# LPC55S69_MINI.net
KiCad netlist of a schematic drawn in Altium Designer
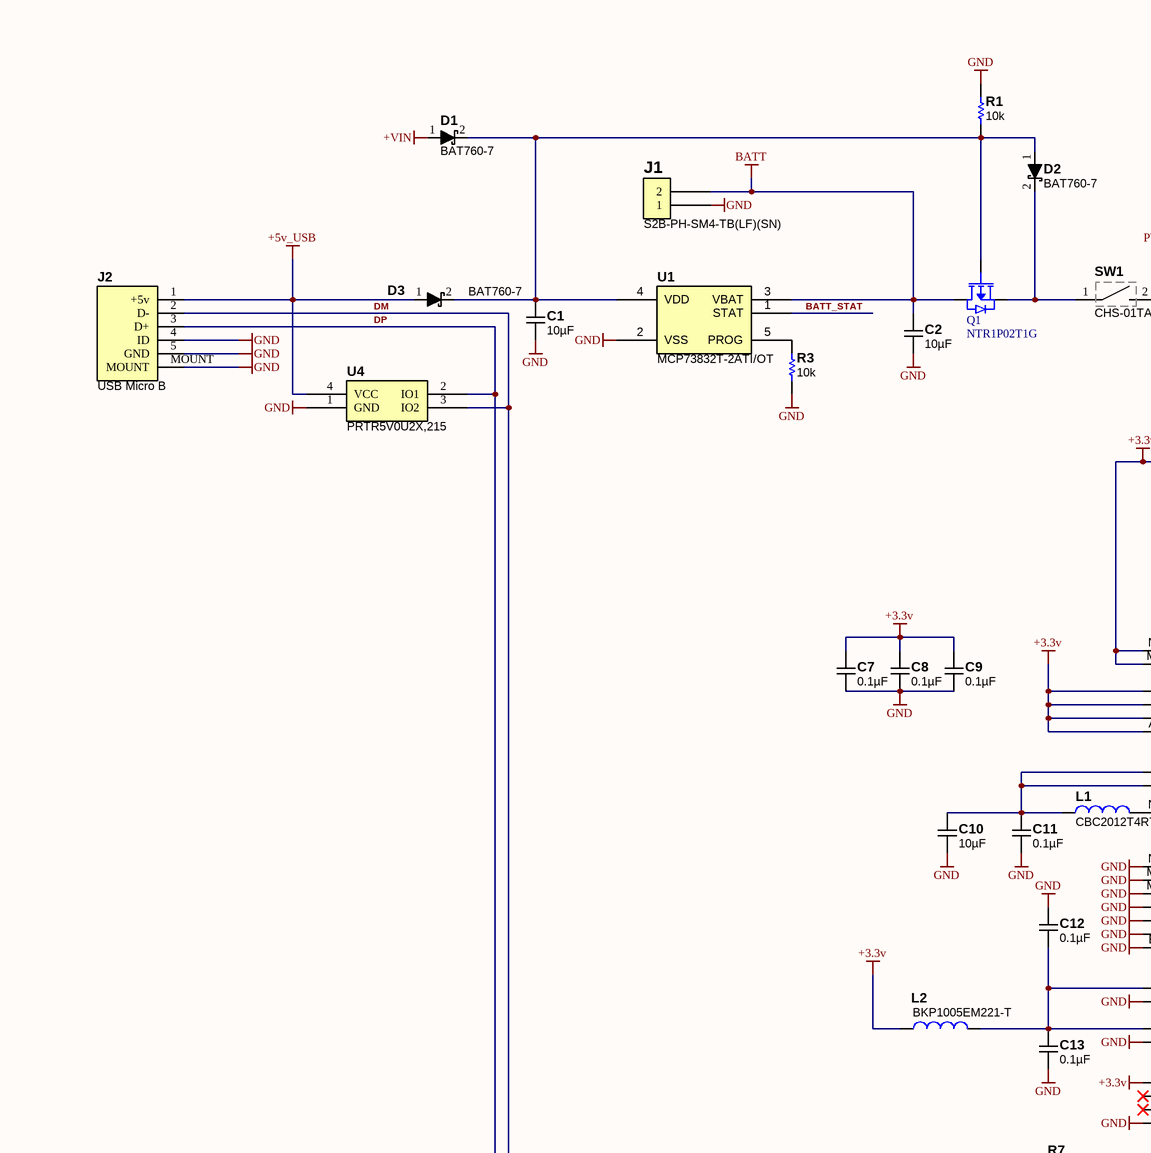
[diagram p0: LPC55S69_MINI.SchDoc, top left]
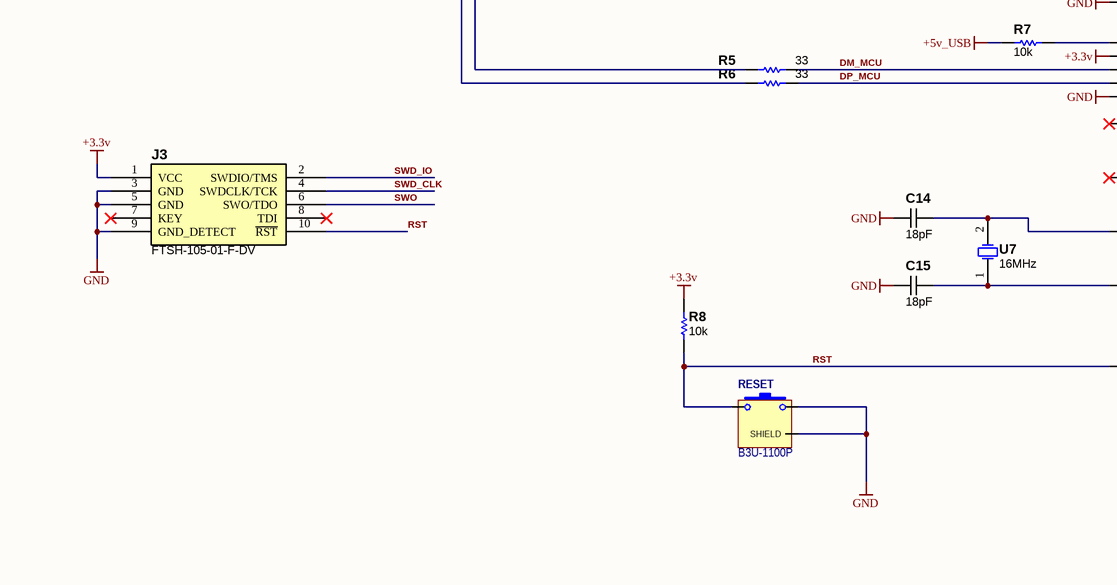
[diagram p1: LPC55S69_MINI.SchDoc, bottom left]
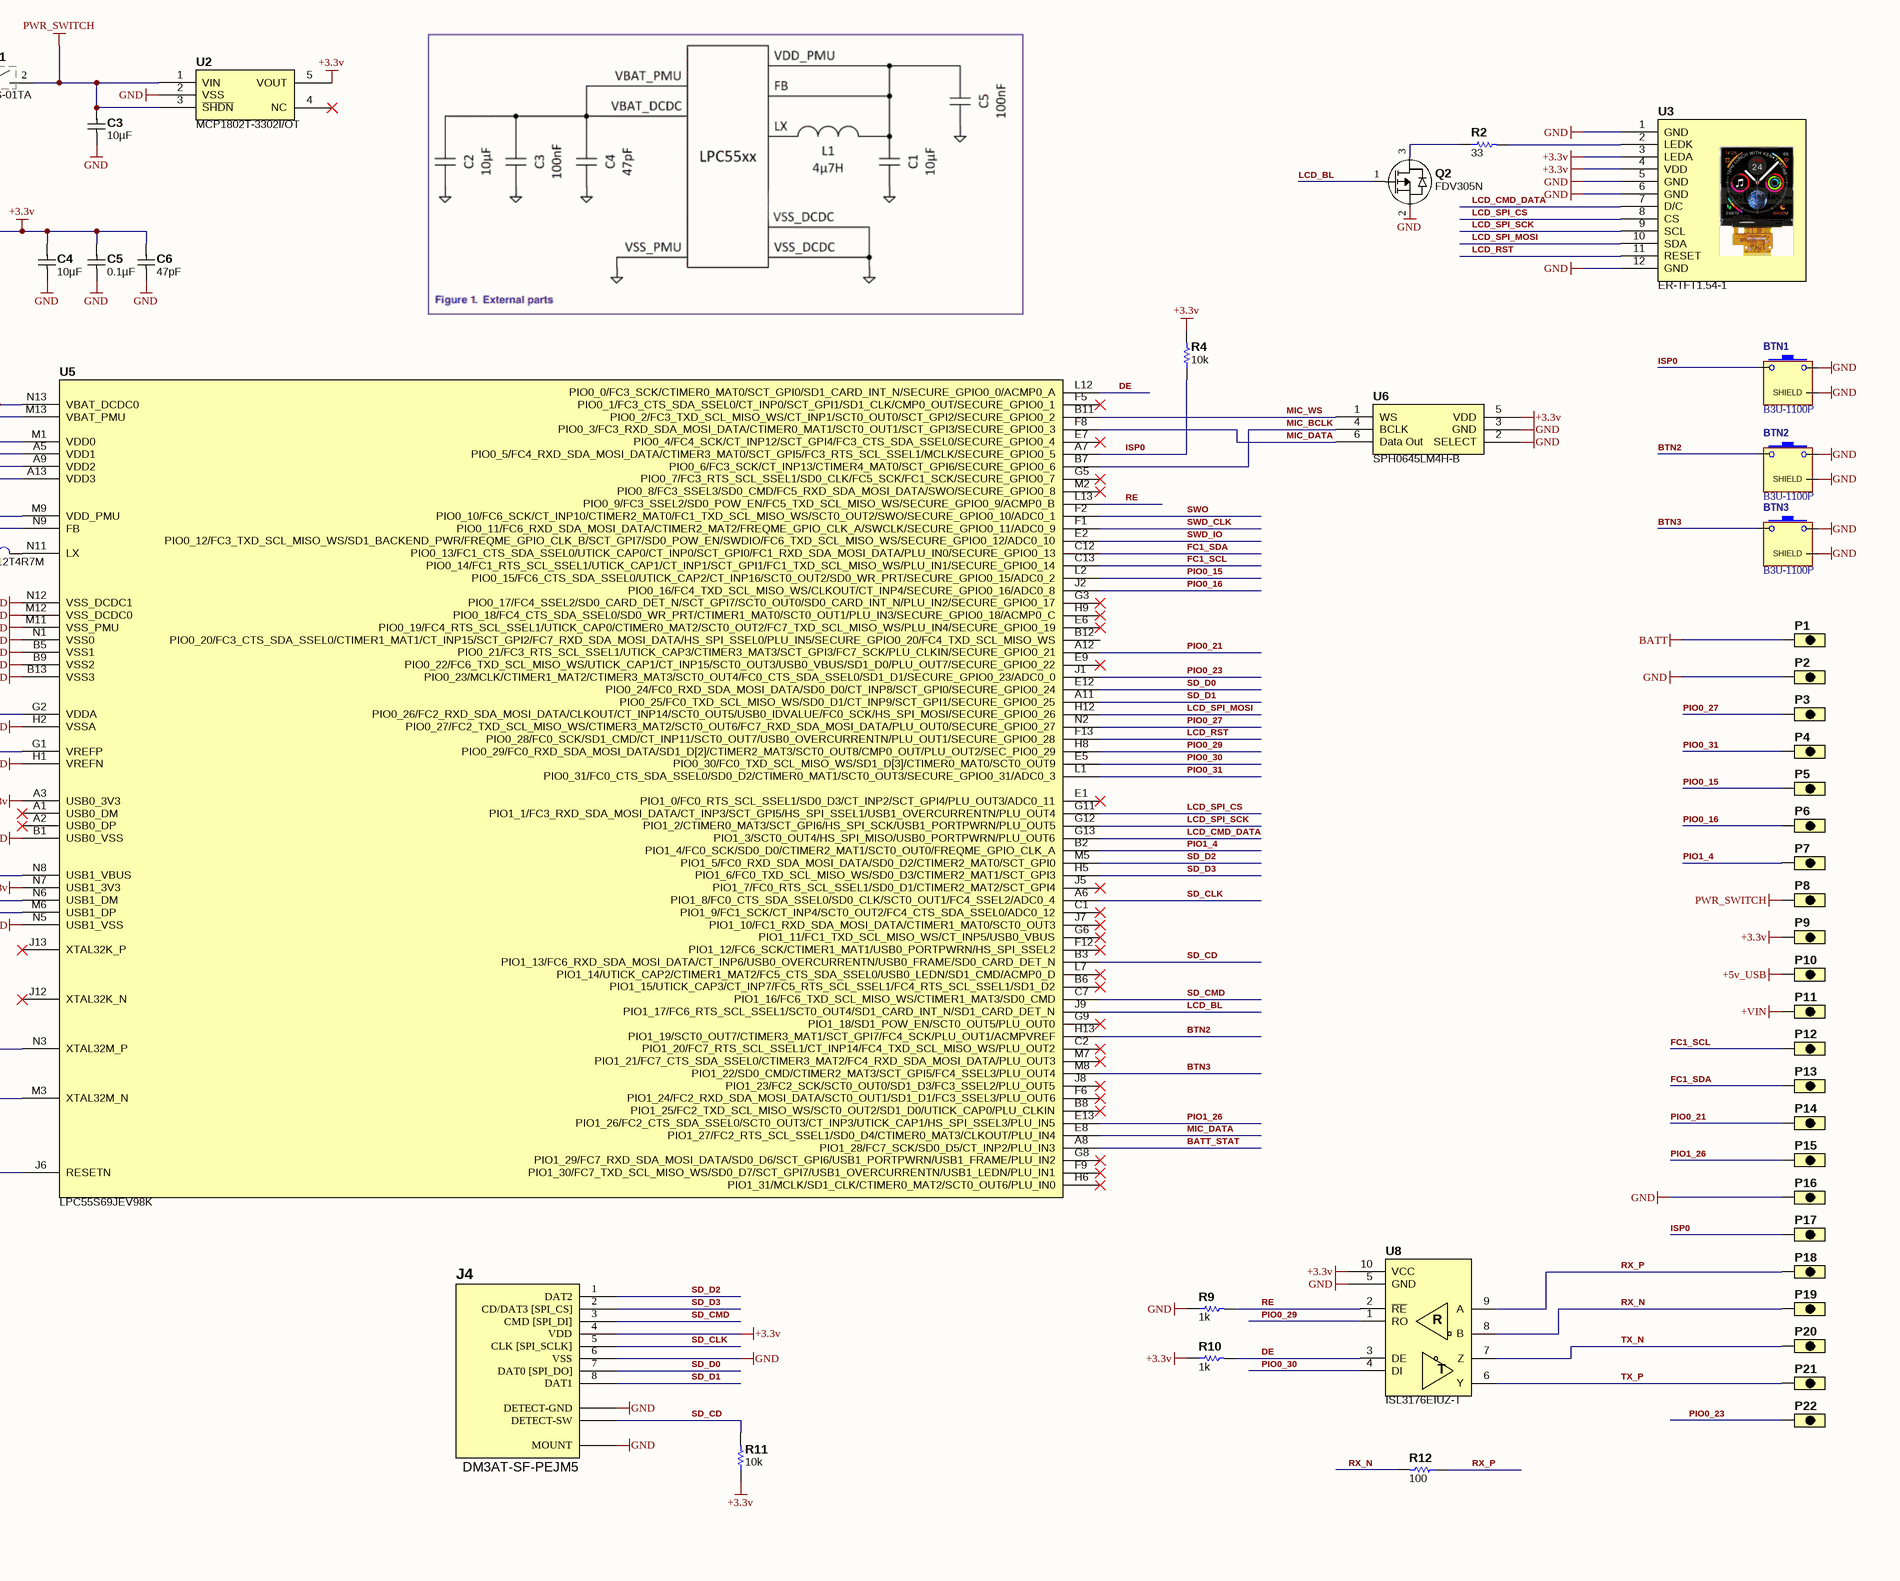
[diagram p2: LPC55S69_MINI.SchDoc, bottom right]

(export (version "E")
  (design (tool "Eeschema 10.0.6"))
  (components
    (comp (ref "BTN1")
      (value "B3U-1100P")
      (footprint "OMRON_B3U-1100P")
      (description "SWITCH TACTILE SPST-NO 0.05A 12V")
      (fields (field (name "MANUFACTURER") "Omron Electronics Inc-EMC Div"))
      (libsource (lib "Switches-N") (part "B3U-1100P"))
    )
    (comp (ref "BTN2")
      (value "B3U-1100P")
      (footprint "OMRON_B3U-1100P")
      (description "SWITCH TACTILE SPST-NO 0.05A 12V")
      (fields (field (name "MANUFACTURER") "Omron Electronics Inc-EMC Div"))
      (libsource (lib "Switches-N") (part "B3U-1100P"))
    )
    (comp (ref "BTN3")
      (value "B3U-1100P")
      (footprint "OMRON_B3U-1100P")
      (description "SWITCH TACTILE SPST-NO 0.05A 12V")
      (fields (field (name "MANUFACTURER") "Omron Electronics Inc-EMC Div"))
      (libsource (lib "Switches-N") (part "B3U-1100P"))
    )
    (comp (ref "C1")
      (value "10µF")
      (footprint "C0805_1.45MM_MD")
      (description "CAP CER 10UF 6.3V X7R 0805")
      (fields
        (field (name "MANUFACTURER PART NUMBER") "CGA4J1X7R0J106K125AC")
        (field (name "MANUFACTURER") "TDK Corporation")
      )
      (libsource (lib "Capacitors - TDK- AEC-Q200") (part "C_2P_NP"))
    )
    (comp (ref "C2")
      (value "10µF")
      (footprint "C0805_1.45MM_MD")
      (description "CAP CER 10UF 6.3V X7R 0805")
      (fields
        (field (name "MANUFACTURER PART NUMBER") "CGA4J1X7R0J106K125AC")
        (field (name "MANUFACTURER") "TDK Corporation")
      )
      (libsource (lib "Capacitors - TDK- AEC-Q200") (part "C_2P_NP"))
    )
    (comp (ref "C3")
      (value "10µF")
      (footprint "C0805_1.45MM_MD")
      (description "CAP CER 10UF 6.3V X7R 0805")
      (fields
        (field (name "MANUFACTURER PART NUMBER") "CGA4J1X7R0J106K125AC")
        (field (name "MANUFACTURER") "TDK Corporation")
      )
      (libsource (lib "Capacitors - TDK- AEC-Q200") (part "C_2P_NP"))
    )
    (comp (ref "C4")
      (value "10µF")
      (footprint "C0805_1.45MM_MD")
      (description "CAP CER 10UF 6.3V X7R 0805")
      (fields
        (field (name "MANUFACTURER PART NUMBER") "CGA4J1X7R0J106K125AC")
        (field (name "MANUFACTURER") "TDK Corporation")
      )
      (libsource (lib "Capacitors - TDK- AEC-Q200") (part "C_2P_NP"))
    )
    (comp (ref "C5")
      (value "0.1µF")
      (footprint "C0402_0.55MM_MD")
      (description "CAP CER 0.1UF 16V X7R 0402")
      (fields
        (field (name "MANUFACTURER PART NUMBER") "CGA2B1X7R1C104K050BC")
        (field (name "MANUFACTURER") "TDK Corporation")
      )
      (libsource (lib "Capacitors - TDK- AEC-Q200") (part "C_2P_NP"))
    )
    (comp (ref "C6")
      (value "47pF")
      (footprint "C0402_0.55MM_MD")
      (description "CAP CER 47PF 50V C0G 0402")
      (fields
        (field (name "MANUFACTURER PART NUMBER") "CGA2B2C0G1H470J050BA")
        (field (name "MANUFACTURER") "TDK Corporation")
      )
      (libsource (lib "Capacitors - TDK- AEC-Q200") (part "C_2P_NP"))
    )
    (comp (ref "C7")
      (value "0.1µF")
      (footprint "C0402_0.55MM_MD")
      (description "CAP CER 0.1UF 16V X7R 0402")
      (fields
        (field (name "MANUFACTURER PART NUMBER") "CGA2B1X7R1C104K050BC")
        (field (name "MANUFACTURER") "TDK Corporation")
      )
      (libsource (lib "Capacitors - TDK- AEC-Q200") (part "C_2P_NP"))
    )
    (comp (ref "C8")
      (value "0.1µF")
      (footprint "C0402_0.55MM_MD")
      (description "CAP CER 0.1UF 16V X7R 0402")
      (fields
        (field (name "MANUFACTURER PART NUMBER") "CGA2B1X7R1C104K050BC")
        (field (name "MANUFACTURER") "TDK Corporation")
      )
      (libsource (lib "Capacitors - TDK- AEC-Q200") (part "C_2P_NP"))
    )
    (comp (ref "C9")
      (value "0.1µF")
      (footprint "C0402_0.55MM_MD")
      (description "CAP CER 0.1UF 16V X7R 0402")
      (fields
        (field (name "MANUFACTURER PART NUMBER") "CGA2B1X7R1C104K050BC")
        (field (name "MANUFACTURER") "TDK Corporation")
      )
      (libsource (lib "Capacitors - TDK- AEC-Q200") (part "C_2P_NP"))
    )
    (comp (ref "C10")
      (value "10µF")
      (footprint "C0805_1.45MM_MD")
      (description "CAP CER 10UF 6.3V X7R 0805")
      (fields
        (field (name "MANUFACTURER PART NUMBER") "CGA4J1X7R0J106K125AC")
        (field (name "MANUFACTURER") "TDK Corporation")
      )
      (libsource (lib "Capacitors - TDK- AEC-Q200") (part "C_2P_NP"))
    )
    (comp (ref "C11")
      (value "0.1µF")
      (footprint "C0402_0.55MM_MD")
      (description "CAP CER 0.1UF 16V X7R 0402")
      (fields
        (field (name "MANUFACTURER PART NUMBER") "CGA2B1X7R1C104K050BC")
        (field (name "MANUFACTURER") "TDK Corporation")
      )
      (libsource (lib "Capacitors - TDK- AEC-Q200") (part "C_2P_NP"))
    )
    (comp (ref "C12")
      (value "0.1µF")
      (footprint "C0402_0.55MM_MD")
      (description "CAP CER 0.1UF 16V X7R 0402")
      (fields
        (field (name "MANUFACTURER PART NUMBER") "CGA2B1X7R1C104K050BC")
        (field (name "MANUFACTURER") "TDK Corporation")
      )
      (libsource (lib "Capacitors - TDK- AEC-Q200") (part "C_2P_NP"))
    )
    (comp (ref "C13")
      (value "0.1µF")
      (footprint "C0402_0.55MM_MD")
      (description "CAP CER 0.1UF 16V X7R 0402")
      (fields
        (field (name "MANUFACTURER PART NUMBER") "CGA2B1X7R1C104K050BC")
        (field (name "MANUFACTURER") "TDK Corporation")
      )
      (libsource (lib "Capacitors - TDK- AEC-Q200") (part "C_2P_NP"))
    )
    (comp (ref "C14")
      (value "18pF")
      (footprint "C0402_0.55MM_MD")
      (description "CAP CER 18PF 50V C0G 0402")
      (fields
        (field (name "MANUFACTURER PART NUMBER") "CGA2B2C0G1H180J050BA")
        (field (name "MANUFACTURER") "TDK Corporation")
      )
      (libsource (lib "Capacitors - TDK- AEC-Q200") (part "C_2P_NP"))
    )
    (comp (ref "C15")
      (value "18pF")
      (footprint "C0402_0.55MM_MD")
      (description "CAP CER 18PF 50V C0G 0402")
      (fields
        (field (name "MANUFACTURER PART NUMBER") "CGA2B2C0G1H180J050BA")
        (field (name "MANUFACTURER") "TDK Corporation")
      )
      (libsource (lib "Capacitors - TDK- AEC-Q200") (part "C_2P_NP"))
    )
    (comp (ref "D1")
      (value "BAT760-7")
      (footprint "D_SOD-323_P")
      (description "DIODE SCHOTTKY 30V 1A SOD323")
      (fields (field (name "MANUFACTURER") "Diodes Inc"))
      (libsource (lib "Diodes") (part "DS_1A_2C"))
    )
    (comp (ref "D2")
      (value "BAT760-7")
      (footprint "D_SOD-323_P")
      (description "DIODE SCHOTTKY 30V 1A SOD323")
      (fields (field (name "MANUFACTURER") "Diodes Inc"))
      (libsource (lib "Diodes") (part "DS_1A_2C"))
    )
    (comp (ref "D3")
      (value "BAT760-7")
      (footprint "D_SOD-323_P")
      (description "DIODE SCHOTTKY 30V 1A SOD323")
      (fields (field (name "MANUFACTURER") "Diodes Inc"))
      (libsource (lib "Diodes") (part "DS_1A_2C"))
    )
    (comp (ref "J1")
      (value "S2B-PH-SM4-TB(LF)(SN)")
      (footprint "S2B-PH-SM4-TB(LF)(SN)")
      (description "CONN HEADER PH SIDE 2POS 2MM SMD")
      (fields (field (name "MANUFACTURER") "JST Sales America Inc"))
      (libsource (lib "eConnector_JST_PH") (part "S2B-PH-SM4-TB(LF)(SN)"))
    )
    (comp (ref "J2")
      (value "USB Micro B")
      (footprint "10103594-0001LF - No Slots")
      (description "CONN RCPT STD MICRO USB TYPE B")
      (fields (field (name "MANUFACTURER") "FCI") (field (name "MANUFACTURER PART NUMBER") "10103594-0001LF"))
      (libsource (lib "eConnector_USB") (part "10103594-0001LF"))
    )
    (comp (ref "J3")
      (value "FTSH-105-01-F-DV")
      (footprint "FTSH-105-01-F-DV-K-A")
      (description "SAMTEC - FTSH-105-01-F-DV - .050 X .050")
      (fields (field (name "MANUFACTURER") "SAMTEC"))
      (libsource (lib "eConnector") (part "CORTEX-DEBUG"))
    )
    (comp (ref "J4")
      (value "DM3AT-SF-PEJM5")
      (footprint "DM3AT-SF-PEJM5")
      (description "CONN MICRO SD R/A PUSH-PUSH SMD")
      (fields (field (name "MANUFACTURER") "Hirose Electric Co Ltd"))
      (libsource (lib "eConnector_SD") (part "DM3AT-SF-PEJM5"))
    )
    (comp (ref "L1")
      (value "CBC2012T4R7M")
      (footprint "C0805_1.45MM_MD")
      (description "FIXED IND 4.7UH 520MA 650 MOHM")
      (fields (field (name "MANUFACTURER") "Taiyo Yuden") (field (name "TOLERANCE") "20%"))
      (libsource (lib "eInductor") (part "CBC2012T4R7M"))
    )
    (comp (ref "L2")
      (value "BKP1005EM221-T")
      (footprint "C0402_HD")
      (description "FERRITE BEAD 220 OHM 0402 1LN")
      (fields (field (name "MANUFACTURER") "Taiyo Yuden"))
      (libsource (lib "eInductor") (part "BKP1005EM221-T"))
    )
    (comp (ref "P1")
      (value "~")
      (footprint "CASTELLATED")
      (libsource (lib "eConnector") (part "CASTELLATED"))
    )
    (comp (ref "P2")
      (value "~")
      (footprint "CASTELLATED")
      (libsource (lib "eConnector") (part "CASTELLATED"))
    )
    (comp (ref "P3")
      (value "~")
      (footprint "CASTELLATED")
      (libsource (lib "eConnector") (part "CASTELLATED"))
    )
    (comp (ref "P4")
      (value "~")
      (footprint "CASTELLATED")
      (libsource (lib "eConnector") (part "CASTELLATED"))
    )
    (comp (ref "P5")
      (value "~")
      (footprint "CASTELLATED")
      (libsource (lib "eConnector") (part "CASTELLATED"))
    )
    (comp (ref "P6")
      (value "~")
      (footprint "CASTELLATED")
      (libsource (lib "eConnector") (part "CASTELLATED"))
    )
    (comp (ref "P7")
      (value "~")
      (footprint "CASTELLATED")
      (libsource (lib "eConnector") (part "CASTELLATED"))
    )
    (comp (ref "P8")
      (value "~")
      (footprint "CASTELLATED")
      (libsource (lib "eConnector") (part "CASTELLATED"))
    )
    (comp (ref "P9")
      (value "~")
      (footprint "CASTELLATED")
      (libsource (lib "eConnector") (part "CASTELLATED"))
    )
    (comp (ref "P10")
      (value "~")
      (footprint "CASTELLATED")
      (libsource (lib "eConnector") (part "CASTELLATED"))
    )
    (comp (ref "P11")
      (value "~")
      (footprint "CASTELLATED")
      (libsource (lib "eConnector") (part "CASTELLATED"))
    )
    (comp (ref "P12")
      (value "~")
      (footprint "CASTELLATED")
      (libsource (lib "eConnector") (part "CASTELLATED"))
    )
    (comp (ref "P13")
      (value "~")
      (footprint "CASTELLATED")
      (libsource (lib "eConnector") (part "CASTELLATED"))
    )
    (comp (ref "P14")
      (value "~")
      (footprint "CASTELLATED")
      (libsource (lib "eConnector") (part "CASTELLATED"))
    )
    (comp (ref "P15")
      (value "~")
      (footprint "CASTELLATED")
      (libsource (lib "eConnector") (part "CASTELLATED"))
    )
    (comp (ref "P16")
      (value "~")
      (footprint "CASTELLATED")
      (libsource (lib "eConnector") (part "CASTELLATED"))
    )
    (comp (ref "P17")
      (value "~")
      (footprint "CASTELLATED")
      (libsource (lib "eConnector") (part "CASTELLATED"))
    )
    (comp (ref "P18")
      (value "~")
      (footprint "CASTELLATED")
      (libsource (lib "eConnector") (part "CASTELLATED"))
    )
    (comp (ref "P19")
      (value "~")
      (footprint "CASTELLATED")
      (libsource (lib "eConnector") (part "CASTELLATED"))
    )
    (comp (ref "P20")
      (value "~")
      (footprint "CASTELLATED")
      (libsource (lib "eConnector") (part "CASTELLATED"))
    )
    (comp (ref "P21")
      (value "~")
      (footprint "CASTELLATED")
      (libsource (lib "eConnector") (part "CASTELLATED"))
    )
    (comp (ref "P22")
      (value "~")
      (footprint "CASTELLATED")
      (libsource (lib "eConnector") (part "CASTELLATED"))
    )
    (comp (ref "Q1")
      (value "NTR1P02T1G")
      (footprint "SOT-23")
      (description "MOSFET P-CH 20V 1A SOT-23")
      (fields (field (name "MANUFACTURER") "ON Semiconductor"))
      (libsource (lib "eTransistor") (part "NTR1P02T1G"))
    )
    (comp (ref "Q2")
      (value "FDV305N")
      (footprint "SOT-23")
      (description "MOSFET N-CH 20V 0.9A SOT-23")
      (fields (field (name "MANUFACTURER") "Fairchild Semiconductor") (field (name "SOURCE") "Digikey"))
      (libsource (lib "wn___Transistor") (part "FDV305"))
    )
    (comp (ref "R1")
      (value "10k")
      (footprint "R0402_0.40MM_MD")
      (description "RES 10K OHM 1/10W 1% 0402 SMD")
      (fields
        (field (name "MANUFACTURER PART NUMBER") "ERJ-2RKF1002X")
        (field (name "MANUFACTURER") "Panasonic Electronic Components")
      )
      (libsource (lib "Resistors - Panasonic - AEC-Q200") (part "R_2P"))
    )
    (comp (ref "R2")
      (value "33")
      (footprint "R0603_0.55MM_MD")
      (description "RES 33 OHM 1/10W 1% 0603 SMD")
      (fields
        (field (name "MANUFACTURER PART NUMBER") "ERJ-3EKF33R0V")
        (field (name "MANUFACTURER") "Panasonic Electronic Components")
      )
      (libsource (lib "Resistors - Panasonic - AEC-Q200") (part "R_2P"))
    )
    (comp (ref "R3")
      (value "10k")
      (footprint "R0402_0.40MM_MD")
      (description "RES 10K OHM 1/10W 1% 0402 SMD")
      (fields
        (field (name "MANUFACTURER PART NUMBER") "ERJ-2RKF1002X")
        (field (name "MANUFACTURER") "Panasonic Electronic Components")
      )
      (libsource (lib "Resistors - Panasonic - AEC-Q200") (part "R_2P"))
    )
    (comp (ref "R4")
      (value "10k")
      (footprint "R0402_0.40MM_MD")
      (description "RES 10K OHM 1/10W 1% 0402 SMD")
      (fields
        (field (name "MANUFACTURER PART NUMBER") "ERJ-2RKF1002X")
        (field (name "MANUFACTURER") "Panasonic Electronic Components")
      )
      (libsource (lib "Resistors - Panasonic - AEC-Q200") (part "R_2P"))
    )
    (comp (ref "R5")
      (value "33")
      (footprint "R0402_0.40MM_MD")
      (description "RES 33 OHM 1/10W 1% 0402 SMD")
      (fields
        (field (name "MANUFACTURER PART NUMBER") "ERJ-2RKF33R0X")
        (field (name "MANUFACTURER") "Panasonic Electronic Components")
      )
      (libsource (lib "Resistors - Panasonic - AEC-Q200") (part "R_2P"))
    )
    (comp (ref "R6")
      (value "33")
      (footprint "R0402_0.40MM_MD")
      (description "RES 33 OHM 1/10W 1% 0402 SMD")
      (fields
        (field (name "MANUFACTURER PART NUMBER") "ERJ-2RKF33R0X")
        (field (name "MANUFACTURER") "Panasonic Electronic Components")
      )
      (libsource (lib "Resistors - Panasonic - AEC-Q200") (part "R_2P"))
    )
    (comp (ref "R7")
      (value "10k")
      (footprint "R0402_0.40MM_MD")
      (description "RES 10K OHM 1/10W 1% 0402 SMD")
      (fields
        (field (name "MANUFACTURER PART NUMBER") "ERJ-2RKF1002X")
        (field (name "MANUFACTURER") "Panasonic Electronic Components")
      )
      (libsource (lib "Resistors - Panasonic - AEC-Q200") (part "R_2P"))
    )
    (comp (ref "R8")
      (value "10k")
      (footprint "R0402_0.40MM_MD")
      (description "RES 10K OHM 1/10W 1% 0402 SMD")
      (fields
        (field (name "MANUFACTURER PART NUMBER") "ERJ-2RKF1002X")
        (field (name "MANUFACTURER") "Panasonic Electronic Components")
      )
      (libsource (lib "Resistors - Panasonic - AEC-Q200") (part "R_2P"))
    )
    (comp (ref "R9")
      (value "1k")
      (footprint "R0402_0.40MM_MD")
      (description "RES 1K OHM 1/10W 1% 0402 SMD")
      (fields
        (field (name "MANUFACTURER PART NUMBER") "ERJ-2RKF1001X")
        (field (name "MANUFACTURER") "Panasonic Electronic Components")
      )
      (libsource (lib "Resistors - Panasonic - AEC-Q200") (part "R_2P"))
    )
    (comp (ref "R10")
      (value "1k")
      (footprint "R0402_0.40MM_MD")
      (description "RES 1K OHM 1/10W 1% 0402 SMD")
      (fields
        (field (name "MANUFACTURER PART NUMBER") "ERJ-2RKF1001X")
        (field (name "MANUFACTURER") "Panasonic Electronic Components")
      )
      (libsource (lib "Resistors - Panasonic - AEC-Q200") (part "R_2P"))
    )
    (comp (ref "R11")
      (value "10k")
      (footprint "R0402_0.40MM_MD")
      (description "RES 10K OHM 1/10W 1% 0402 SMD")
      (fields
        (field (name "MANUFACTURER PART NUMBER") "ERJ-2RKF1002X")
        (field (name "MANUFACTURER") "Panasonic Electronic Components")
      )
      (libsource (lib "Resistors - Panasonic - AEC-Q200") (part "R_2P"))
    )
    (comp (ref "R12")
      (value "100")
      (footprint "R0603_HD")
      (description "RES 100 OHM 1/10W 1% 0603 SMD")
      (fields
        (field (name "MANUFACTURER PART NUMBER") "ERJ-3EKF1000V")
        (field (name "MANUFACTURER") "Panasonic Electronic Components")
      )
      (libsource (lib "Resistors - Panasonic - AEC-Q200") (part "R_2P"))
    )
    (comp (ref "RESET")
      (value "B3U-1100P")
      (footprint "OMRON_B3U-1100P")
      (description "SWITCH TACTILE SPST-NO 0.05A 12V")
      (fields (field (name "MANUFACTURER") "Omron Electronics Inc-EMC Div"))
      (libsource (lib "Switches-N") (part "B3U-1100P"))
    )
    (comp (ref "SW1")
      (value "CHS-01TA")
      (footprint "CHS-01TA")
      (description "NIDEC COPAL ELECTRONICS - CHS-01TA - DIP SWITCH, 1POS, SPST, SLIDE, SMD")
      (fields (field (name "MANUFACTURER") "Nidec Copal"))
      (libsource (lib "eElectroMechanical") (part "CHS-01TA"))
    )
    (comp (ref "U1")
      (value "MCP73832T-2ATI/OT")
      (footprint "SOT23-5")
      (description "Charge Controller Li-Ion/Li-Pol 15mA to 500mA 4.2V 5-Pin SOT-23 T/R")
      (fields (field (name "MANUFACTURER") "Microchip"))
      (libsource (lib "eIC") (part "MCP73832T-2ATI/OT"))
    )
    (comp (ref "U2")
      (value "MCP1802T-3302I/OT")
      (footprint "SOT23-5")
      (description "IC REG LINEAR 3.3V 300MA SOT23-5")
      (fields (field (name "MANUFACTURER") "Microchip"))
      (libsource (lib "eIC_Regulator") (part "MCP1802T-3302I/OT"))
    )
    (comp (ref "U3")
      (value "ER-TFT1.54-1")
      (footprint "ER-TFT1.54-1")
      (description "1.54\" 240x240 IPS Display")
      (fields (field (name "MANUFACTURER") "Buy Display"))
      (libsource (lib "eDisplay") (part "ER-TFT1.54-1"))
    )
    (comp (ref "U4")
      (value "PRTR5V0U2X,215")
      (footprint "SOT143B")
      (description "TVS DIODE 5.5VWM SOT143B")
      (fields (field (name "MANUFACTURER") "NXP Semiconductors"))
      (libsource (lib "eDiode") (part "PRTR5V0U2X,215"))
    )
    (comp (ref "U5")
      (value "LPC55S69JEV98K")
      (footprint "98-VFBGA")
      (description "IC MCU 100MHZ CORTEX M33 DUAL")
      (fields (field (name "MANUFACTURER") "NXP Semiconductors"))
      (libsource (lib "eIC") (part "LPC55S69JEV98K"))
    )
    (comp (ref "U6")
      (value "SPH0645LM4H-B")
      (footprint "SPH0645LM4H-B")
      (fields (field (name "MANUFACTURER") "Knowles Acoustics"))
      (libsource (lib "eAudio") (part "SPH0645LM4H-B"))
    )
    (comp (ref "U7")
      (value "16MHz")
      (footprint "ABM3")
      (description "Crystal 16MHz ±20ppm (Tol) ±50ppm (Stability) 18pF FUND 50Ohm 2-Pin CSMD T/R")
      (fields
        (field (name "MANUFACTURER") "Abracon")
        (field (name "MANUFACTURER PART NUMBER") "ABM3-16.000MHZ-B2-T")
      )
      (libsource (lib "eCrystal") (part "ABM3-16.000MHZ-B2-T"))
    )
    (comp (ref "U8")
      (value "ISL3176EIUZ-T")
      (footprint "10 MSOP")
      (description "IC TXRX RS422/485 20MBPS 10MSOP")
      (fields (field (name "MANUFACTURER") "Intersil"))
      (libsource (lib "eIC") (part "ISL3176EIUZ-T"))
    )
  )
  (nets
    (net (code "1") (name "+3.3v") (class "Default")
      (node (ref "C4") (pin "2") (pinfunction "1_2") (pintype "passive"))
      (node (ref "C5") (pin "2") (pinfunction "1_2") (pintype "passive"))
      (node (ref "C6") (pin "2") (pinfunction "1_2") (pintype "passive"))
      (node (ref "C7") (pin "2") (pinfunction "1_2") (pintype "passive"))
      (node (ref "C8") (pin "2") (pinfunction "1_2") (pintype "passive"))
      (node (ref "C9") (pin "2") (pinfunction "1_2") (pintype "passive"))
      (node (ref "J3") (pin "1") (pinfunction "VCC_1") (pintype "passive"))
      (node (ref "J4") (pin "4") (pinfunction "VDD_4") (pintype "passive"))
      (node (ref "L2") (pin "1") (pinfunction "1_1") (pintype "passive"))
      (node (ref "P9") (pin "1") (pinfunction "1_1") (pintype "passive"))
      (node (ref "R10") (pin "1") (pinfunction "1_1") (pintype "passive"))
      (node (ref "R11") (pin "1") (pinfunction "1_1") (pintype "passive"))
      (node (ref "R4") (pin "2") (pinfunction "2_2") (pintype "passive"))
      (node (ref "R8") (pin "2") (pinfunction "2_2") (pintype "passive"))
      (node (ref "U2") (pin "5") (pinfunction "VOUT_5") (pintype "passive"))
      (node (ref "U3") (pin "3") (pinfunction "LEDA_3") (pintype "passive"))
      (node (ref "U3") (pin "4") (pinfunction "VDD_4") (pintype "passive"))
      (node (ref "U5") (pin "A13") (pinfunction "VDD3_A13") (pintype "passive"))
      (node (ref "U5") (pin "A3") (pinfunction "USB0_3V3_A3") (pintype "passive"))
      (node (ref "U5") (pin "A5") (pinfunction "VDD1_A5") (pintype "passive"))
      (node (ref "U5") (pin "A9") (pinfunction "VDD2_A9") (pintype "passive"))
      (node (ref "U5") (pin "M1") (pinfunction "VDD0_M1") (pintype "passive"))
      (node (ref "U5") (pin "M13") (pinfunction "VBAT_PMU_M13") (pintype "passive"))
      (node (ref "U5") (pin "N13") (pinfunction "VBAT_DCDC0_N13") (pintype "passive"))
      (node (ref "U5") (pin "N7") (pinfunction "USB1_3V3_N7") (pintype "passive"))
      (node (ref "U6") (pin "5") (pinfunction "VDD_5") (pintype "passive"))
      (node (ref "U8") (pin "10") (pinfunction "VCC_10") (pintype "passive"))
    )
    (net (code "2") (name "+5v_USB") (class "Default")
      (node (ref "D3") (pin "1") (pinfunction "A_1") (pintype "passive"))
      (node (ref "J2") (pin "1") (pinfunction "+5v_1") (pintype "passive"))
      (node (ref "P10") (pin "1") (pinfunction "1_1") (pintype "passive"))
      (node (ref "R7") (pin "2") (pinfunction "2_2") (pintype "passive"))
      (node (ref "U4") (pin "4") (pinfunction "VCC_4") (pintype "passive"))
    )
    (net (code "3") (name "+VIN") (class "Default")
      (node (ref "D1") (pin "1") (pinfunction "A_1") (pintype "passive"))
      (node (ref "P11") (pin "1") (pinfunction "1_1") (pintype "passive"))
    )
    (net (code "4") (name "/BATT_STAT") (class "Default")
      (node (ref "U1") (pin "1") (pinfunction "STAT_1") (pintype "passive"))
      (node (ref "U5") (pin "A8") (pinfunction "PIO1_28/FC7_SCK/SD0_D5/CT_INP2/PLU_IN3_A8") (pintype "passive"))
    )
    (net (code "5") (name "/BTN2") (class "Default")
      (node (ref "BTN2") (pin "2") (pinfunction "2_2") (pintype "passive"))
      (node (ref "U5") (pin "H13") (pinfunction "PIO1_19/SCT0_OUT7/CTIMER3_MAT1/SCT_GPI7/FC4_SCK/PLU_OUT1/ACMPVREF_H13") (pintype "passive"))
    )
    (net (code "6") (name "/BTN3") (class "Default")
      (node (ref "BTN3") (pin "2") (pinfunction "2_2") (pintype "passive"))
      (node (ref "U5") (pin "M8") (pinfunction "PIO1_22/SD0_CMD/CTIMER2_MAT3/SCT_GPI5/FC4_SSEL3/PLU_OUT4_M8") (pintype "passive"))
    )
    (net (code "7") (name "/DE") (class "Default")
      (node (ref "R10") (pin "2") (pinfunction "2_2") (pintype "passive"))
      (node (ref "U5") (pin "L12") (pinfunction "PIO0_0/FC3_SCK/CTIMER0_MAT0/SCT_GPI0/SD1_CARD_INT_N/SECURE_GPIO0_0/ACMP0_A_L12") (pintype "passive"))
      (node (ref "U8") (pin "3") (pinfunction "DE_3") (pintype "passive"))
    )
    (net (code "8") (name "/DM") (class "Default")
      (node (ref "J2") (pin "2") (pinfunction "D-_2") (pintype "passive"))
      (node (ref "R5") (pin "1") (pinfunction "1_1") (pintype "passive"))
      (node (ref "U4") (pin "3") (pinfunction "IO2_3") (pintype "passive"))
    )
    (net (code "9") (name "/DM_MCU") (class "Default")
      (node (ref "R5") (pin "2") (pinfunction "2_2") (pintype "passive"))
      (node (ref "U5") (pin "N6") (pinfunction "USB1_DM_N6") (pintype "passive"))
    )
    (net (code "10") (name "/DP") (class "Default")
      (node (ref "J2") (pin "3") (pinfunction "D+_3") (pintype "passive"))
      (node (ref "R6") (pin "1") (pinfunction "1_1") (pintype "passive"))
      (node (ref "U4") (pin "2") (pinfunction "IO1_2") (pintype "passive"))
    )
    (net (code "11") (name "/DP_MCU") (class "Default")
      (node (ref "R6") (pin "2") (pinfunction "2_2") (pintype "passive"))
      (node (ref "U5") (pin "M6") (pinfunction "USB1_DP_M6") (pintype "passive"))
    )
    (net (code "12") (name "/FC1_SCL") (class "Default")
      (node (ref "P12") (pin "1") (pinfunction "1_1") (pintype "passive"))
      (node (ref "U5") (pin "C13") (pinfunction "PIO0_14/FC1_RTS_SCL_SSEL1/UTICK_CAP1/CT_INP1/SCT_GPI1/FC1_TXD_SCL_MISO_WS/PLU_IN1/SECURE_GPIO0_14_C13") (pintype "passive"))
    )
    (net (code "13") (name "/FC1_SDA") (class "Default")
      (node (ref "P13") (pin "1") (pinfunction "1_1") (pintype "passive"))
      (node (ref "U5") (pin "C12") (pinfunction "PIO0_13/FC1_CTS_SDA_SSEL0/UTICK_CAP0/CT_INP0/SCT_GPI0/FC1_RXD_SDA_MOSI_DATA/PLU_IN0/SECURE_GPIO0_13_C12") (pintype "passive"))
    )
    (net (code "14") (name "/ISP0") (class "Default")
      (node (ref "BTN1") (pin "2") (pinfunction "2_2") (pintype "passive"))
      (node (ref "P17") (pin "1") (pinfunction "1_1") (pintype "passive"))
      (node (ref "R4") (pin "1") (pinfunction "1_1") (pintype "passive"))
      (node (ref "U5") (pin "A7") (pinfunction "PIO0_5/FC4_RXD_SDA_MOSI_DATA/CTIMER3_MAT0/SCT_GPI5/FC3_RTS_SCL_SSEL1/MCLK/SECURE_GPIO0_5_A7") (pintype "passive"))
    )
    (net (code "15") (name "/LCD_BL") (class "Default")
      (node (ref "Q2") (pin "1") (pinfunction "G_1") (pintype "passive"))
      (node (ref "U5") (pin "J9") (pinfunction "PIO1_17/FC6_RTS_SCL_SSEL1/SCT0_OUT4/SD1_CARD_INT_N/SD1_CARD_DET_N_J9") (pintype "passive"))
    )
    (net (code "16") (name "/LCD_CMD_DATA") (class "Default")
      (node (ref "U3") (pin "7") (pinfunction "D/C_7") (pintype "passive"))
      (node (ref "U5") (pin "G13") (pinfunction "PIO1_3/SCT0_OUT4/HS_SPI_MISO/USB0_PORTPWRN/PLU_OUT6_G13") (pintype "passive"))
    )
    (net (code "17") (name "/LCD_RST") (class "Default")
      (node (ref "U3") (pin "11") (pinfunction "RESET_11") (pintype "passive"))
      (node (ref "U5") (pin "F13") (pinfunction "PIO0_28/FC0_SCK/SD1_CMD/CT_INP11/SCT0_OUT7/USB0_OVERCURRENTN/PLU_OUT1/SECURE_GPIO0_28_F13") (pintype "passive"))
    )
    (net (code "18") (name "/LCD_SPI_CS") (class "Default")
      (node (ref "U3") (pin "8") (pinfunction "CS_8") (pintype "passive"))
      (node (ref "U5") (pin "G11") (pinfunction "PIO1_1/FC3_RXD_SDA_MOSI_DATA/CT_INP3/SCT_GPI5/HS_SPI_SSEL1/USB1_OVERCURRENTN/PLU_OUT4_G11") (pintype "passive"))
    )
    (net (code "19") (name "/LCD_SPI_MOSI") (class "Default")
      (node (ref "U3") (pin "10") (pinfunction "SDA_10") (pintype "passive"))
      (node (ref "U5") (pin "H12") (pinfunction "PIO0_26/FC2_RXD_SDA_MOSI_DATA/CLKOUT/CT_INP14/SCT0_OUT5/USB0_IDVALUE/FC0_SCK/HS_SPI_MOSI/SECURE_GPIO0_26_H12") (pintype "passive"))
    )
    (net (code "20") (name "/LCD_SPI_SCK") (class "Default")
      (node (ref "U3") (pin "9") (pinfunction "SCL_9") (pintype "passive"))
      (node (ref "U5") (pin "G12") (pinfunction "PIO1_2/CTIMER0_MAT3/SCT_GPI6/HS_SPI_SCK/USB1_PORTPWRN/PLU_OUT5_G12") (pintype "passive"))
    )
    (net (code "21") (name "/MIC_BCLK") (class "Default")
      (node (ref "U5") (pin "B7") (pinfunction "PIO0_6/FC3_SCK/CT_INP13/CTIMER4_MAT0/SCT_GPI6/SECURE_GPIO0_6_B7") (pintype "passive"))
      (node (ref "U6") (pin "4") (pinfunction "BCLK_4") (pintype "passive"))
    )
    (net (code "22") (name "/MIC_DATA") (class "Default")
      (node (ref "U5") (pin "E8") (pinfunction "PIO1_27/FC2_RTS_SCL_SSEL1/SD0_D4/CTIMER0_MAT3/CLKOUT/PLU_IN4_E8") (pintype "passive"))
      (node (ref "U5") (pin "F8") (pinfunction "PIO0_3/FC3_RXD_SDA_MOSI_DATA/CTIMER0_MAT1/SCT0_OUT1/SCT_GPI3/SECURE_GPIO0_3_F8") (pintype "passive"))
      (node (ref "U6") (pin "6") (pinfunction "Data_Out_6") (pintype "passive"))
    )
    (net (code "23") (name "/MIC_WS") (class "Default")
      (node (ref "U5") (pin "B11") (pinfunction "PIO0_2/FC3_TXD_SCL_MISO_WS/CT_INP1/SCT0_OUT0/SCT_GPI2/SECURE_GPIO0_2_B11") (pintype "passive"))
      (node (ref "U6") (pin "1") (pinfunction "WS_1") (pintype "passive"))
    )
    (net (code "24") (name "/PIO0_15") (class "Default")
      (node (ref "P5") (pin "1") (pinfunction "1_1") (pintype "passive"))
      (node (ref "U5") (pin "L2") (pinfunction "PIO0_15/FC6_CTS_SDA_SSEL0/UTICK_CAP2/CT_INP16/SCT0_OUT2/SD0_WR_PRT/SECURE_GPIO0_15/ADC0_2_L2") (pintype "passive"))
    )
    (net (code "25") (name "/PIO0_16") (class "Default")
      (node (ref "P6") (pin "1") (pinfunction "1_1") (pintype "passive"))
      (node (ref "U5") (pin "J2") (pinfunction "PIO0_16/FC4_TXD_SCL_MISO_WS/CLKOUT/CT_INP4/SECURE_GPIO0_16/ADC0_8_J2") (pintype "passive"))
    )
    (net (code "26") (name "/PIO0_21") (class "Default")
      (node (ref "P14") (pin "1") (pinfunction "1_1") (pintype "passive"))
      (node (ref "U5") (pin "A12") (pinfunction "PIO0_21/FC3_RTS_SCL_SSEL1/UTICK_CAP3/CTIMER3_MAT3/SCT_GPI3/FC7_SCK/PLU_CLKIN/SECURE_GPIO0_21_A12") (pintype "passive"))
    )
    (net (code "27") (name "/PIO0_23") (class "Default")
      (node (ref "P22") (pin "1") (pinfunction "1_1") (pintype "passive"))
      (node (ref "U5") (pin "J1") (pinfunction "PIO0_23/MCLK/CTIMER1_MAT2/CTIMER3_MAT3/SCT0_OUT4/FC0_CTS_SDA_SSEL0/SD1_D1/SECURE_GPIO0_23/ADC0_0_J1") (pintype "passive"))
    )
    (net (code "28") (name "/PIO0_27") (class "Default")
      (node (ref "P3") (pin "1") (pinfunction "1_1") (pintype "passive"))
      (node (ref "U5") (pin "N2") (pinfunction "PIO0_27/FC2_TXD_SCL_MISO_WS/CTIMER3_MAT2/SCT0_OUT6/FC7_RXD_SDA_MOSI_DATA/PLU_OUT0/SECURE_GPIO0_27_N2") (pintype "passive"))
    )
    (net (code "29") (name "/PIO0_29") (class "Default")
      (node (ref "U5") (pin "H8") (pinfunction "PIO0_29/FC0_RXD_SDA_MOSI_DATA/SD1_D[2]/CTIMER2_MAT3/SCT0_OUT8/CMP0_OUT/PLU_OUT2/SEC_PIO0_29_H8") (pintype "passive"))
      (node (ref "U8") (pin "1") (pinfunction "RO_1") (pintype "passive"))
    )
    (net (code "30") (name "/PIO0_30") (class "Default")
      (node (ref "U5") (pin "E5") (pinfunction "PIO0_30/FC0_TXD_SCL_MISO_WS/SD1_D[3]/CTIMER0_MAT0/SCT0_OUT9_E5") (pintype "passive"))
      (node (ref "U8") (pin "4") (pinfunction "DI_4") (pintype "passive"))
    )
    (net (code "31") (name "/PIO0_31") (class "Default")
      (node (ref "P4") (pin "1") (pinfunction "1_1") (pintype "passive"))
      (node (ref "U5") (pin "L1") (pinfunction "PIO0_31/FC0_CTS_SDA_SSEL0/SD0_D2/CTIMER0_MAT1/SCT0_OUT3/SECURE_GPIO0_31/ADC0_3_L1") (pintype "passive"))
    )
    (net (code "32") (name "/PIO1_4") (class "Default")
      (node (ref "P7") (pin "1") (pinfunction "1_1") (pintype "passive"))
      (node (ref "U5") (pin "B2") (pinfunction "PIO1_4/FC0_SCK/SD0_D0/CTIMER2_MAT1/SCT0_OUT0/FREQME_GPIO_CLK_A_B2") (pintype "passive"))
    )
    (net (code "33") (name "/PIO1_26") (class "Default")
      (node (ref "P15") (pin "1") (pinfunction "1_1") (pintype "passive"))
      (node (ref "U5") (pin "E13") (pinfunction "PIO1_26/FC2_CTS_SDA_SSEL0/SCT0_OUT3/CT_INP3/UTICK_CAP1/HS_SPI_SSEL3/PLU_IN5_E13") (pintype "passive"))
    )
    (net (code "34") (name "/RE") (class "Default")
      (node (ref "R9") (pin "2") (pinfunction "2_2") (pintype "passive"))
      (node (ref "U5") (pin "L13") (pinfunction "PIO0_9/FC3_SSEL2/SD0_POW_EN/FC5_TXD_SCL_MISO_WS/SECURE_GPIO0_9/ACMP0_B_L13") (pintype "passive"))
      (node (ref "U8") (pin "2") (pinfunction "~{RE}_2") (pintype "passive"))
    )
    (net (code "35") (name "/RST") (class "Default")
      (node (ref "J3") (pin "10") (pinfunction "~{RST}_10") (pintype "passive"))
      (node (ref "R8") (pin "1") (pinfunction "1_1") (pintype "passive"))
      (node (ref "RESET") (pin "2") (pinfunction "2_2") (pintype "passive"))
      (node (ref "U5") (pin "J6") (pinfunction "RESETN_J6") (pintype "passive"))
    )
    (net (code "36") (name "/RX_N") (class "Default")
      (node (ref "P19") (pin "1") (pinfunction "1_1") (pintype "passive"))
      (node (ref "R12") (pin "2") (pinfunction "2_2") (pintype "passive"))
      (node (ref "U8") (pin "8") (pinfunction "B_8") (pintype "passive"))
    )
    (net (code "37") (name "/RX_P") (class "Default")
      (node (ref "P18") (pin "1") (pinfunction "1_1") (pintype "passive"))
      (node (ref "R12") (pin "1") (pinfunction "1_1") (pintype "passive"))
      (node (ref "U8") (pin "9") (pinfunction "A_9") (pintype "passive"))
    )
    (net (code "38") (name "/SD_CD") (class "Default")
      (node (ref "J4") (pin "CDB") (pinfunction "DETECT-SW_CDB") (pintype "passive"))
      (node (ref "R11") (pin "2") (pinfunction "2_2") (pintype "passive"))
      (node (ref "U5") (pin "B3") (pinfunction "PIO1_13/FC6_RXD_SDA_MOSI_DATA/CT_INP6/USB0_OVERCURRENTN/USB0_FRAME/SD0_CARD_DET_N_B3") (pintype "passive"))
    )
    (net (code "39") (name "/SD_CLK") (class "Default")
      (node (ref "J4") (pin "5") (pinfunction "CLK_[SPI_SCLK]_5") (pintype "passive"))
      (node (ref "U5") (pin "A6") (pinfunction "PIO1_8/FC0_CTS_SDA_SSEL0/SD0_CLK/SCT0_OUT1/FC4_SSEL2/ADC0_4_A6") (pintype "passive"))
    )
    (net (code "40") (name "/SD_CMD") (class "Default")
      (node (ref "J4") (pin "3") (pinfunction "CMD_[SPI_DI]_3") (pintype "passive"))
      (node (ref "U5") (pin "C7") (pinfunction "PIO1_16/FC6_TXD_SCL_MISO_WS/CTIMER1_MAT3/SD0_CMD_C7") (pintype "passive"))
    )
    (net (code "41") (name "/SD_D0") (class "Default")
      (node (ref "J4") (pin "7") (pinfunction "DAT0_[SPI_DO]_7") (pintype "passive"))
      (node (ref "U5") (pin "E12") (pinfunction "PIO0_24/FC0_RXD_SDA_MOSI_DATA/SD0_D0/CT_INP8/SCT_GPI0/SECURE_GPIO0_24_E12") (pintype "passive"))
    )
    (net (code "42") (name "/SD_D1") (class "Default")
      (node (ref "J4") (pin "8") (pinfunction "DAT1_8") (pintype "passive"))
      (node (ref "U5") (pin "A11") (pinfunction "PIO0_25/FC0_TXD_SCL_MISO_WS/SD0_D1/CT_INP9/SCT_GPI1/SECURE_GPIO0_25_A11") (pintype "passive"))
    )
    (net (code "43") (name "/SD_D2") (class "Default")
      (node (ref "J4") (pin "1") (pinfunction "DAT2_1") (pintype "passive"))
      (node (ref "U5") (pin "M5") (pinfunction "PIO1_5/FC0_RXD_SDA_MOSI_DATA/SD0_D2/CTIMER2_MAT0/SCT_GPI0_M5") (pintype "passive"))
    )
    (net (code "44") (name "/SD_D3") (class "Default")
      (node (ref "J4") (pin "2") (pinfunction "CD/DAT3_[SPI_CS]_2") (pintype "passive"))
      (node (ref "U5") (pin "H5") (pinfunction "PIO1_6/FC0_TXD_SCL_MISO_WS/SD0_D3/CTIMER2_MAT1/SCT_GPI3_H5") (pintype "passive"))
    )
    (net (code "45") (name "/SWD_CLK") (class "Default")
      (node (ref "J3") (pin "4") (pinfunction "SWDCLK/TCK_4") (pintype "passive"))
      (node (ref "U5") (pin "F1") (pinfunction "PIO0_11/FC6_RXD_SDA_MOSI_DATA/CTIMER2_MAT2/FREQME_GPIO_CLK_A/SWCLK/SECURE_GPIO0_11/ADC0_9_F1") (pintype "passive"))
    )
    (net (code "46") (name "/SWD_IO") (class "Default")
      (node (ref "J3") (pin "2") (pinfunction "SWDIO/TMS_2") (pintype "passive"))
      (node (ref "U5") (pin "E2") (pinfunction "PIO0_12/FC3_TXD_SCL_MISO_WS/SD1_BACKEND_PWR/FREQME_GPIO_CLK_B/SCT_GPI7/SD0_POW_EN/SWDIO/FC6_TXD_SCL_MISO_WS/SECURE_GPIO0_12/ADC0_10_E2") (pintype "passive"))
    )
    (net (code "47") (name "/SWO") (class "Default")
      (node (ref "J3") (pin "6") (pinfunction "SWO/TDO_6") (pintype "passive"))
      (node (ref "U5") (pin "F2") (pinfunction "PIO0_10/FC6_SCK/CT_INP10/CTIMER2_MAT0/FC1_TXD_SCL_MISO_WS/SCT0_OUT2/SWO/SECURE_GPIO0_10/ADC0_1_F2") (pintype "passive"))
    )
    (net (code "48") (name "/TX_N") (class "Default")
      (node (ref "P20") (pin "1") (pinfunction "1_1") (pintype "passive"))
      (node (ref "U8") (pin "7") (pinfunction "Z_7") (pintype "passive"))
    )
    (net (code "49") (name "/TX_P") (class "Default")
      (node (ref "P21") (pin "1") (pinfunction "1_1") (pintype "passive"))
      (node (ref "U8") (pin "6") (pinfunction "Y_6") (pintype "passive"))
    )
    (net (code "50") (name "BATT") (class "Default")
      (node (ref "C2") (pin "2") (pinfunction "1_2") (pintype "passive"))
      (node (ref "J1") (pin "2") (pinfunction "2_2") (pintype "passive"))
      (node (ref "P1") (pin "1") (pinfunction "1_1") (pintype "passive"))
      (node (ref "Q1") (pin "3") (pinfunction "D_3") (pintype "passive"))
      (node (ref "U1") (pin "3") (pinfunction "VBAT_3") (pintype "passive"))
    )
    (net (code "51") (name "GND") (class "Default")
      (node (ref "BTN1") (pin "1") (pinfunction "1_1") (pintype "passive"))
      (node (ref "BTN1") (pin "S") (pinfunction "SHIELD_S") (pintype "passive"))
      (node (ref "BTN2") (pin "1") (pinfunction "1_1") (pintype "passive"))
      (node (ref "BTN2") (pin "S") (pinfunction "SHIELD_S") (pintype "passive"))
      (node (ref "BTN3") (pin "1") (pinfunction "1_1") (pintype "passive"))
      (node (ref "BTN3") (pin "S") (pinfunction "SHIELD_S") (pintype "passive"))
      (node (ref "C1") (pin "1") (pinfunction "1_1") (pintype "passive"))
      (node (ref "C10") (pin "1") (pinfunction "1_1") (pintype "passive"))
      (node (ref "C11") (pin "1") (pinfunction "1_1") (pintype "passive"))
      (node (ref "C12") (pin "2") (pinfunction "1_2") (pintype "passive"))
      (node (ref "C13") (pin "1") (pinfunction "1_1") (pintype "passive"))
      (node (ref "C14") (pin "1") (pinfunction "1_1") (pintype "passive"))
      (node (ref "C15") (pin "1") (pinfunction "1_1") (pintype "passive"))
      (node (ref "C2") (pin "1") (pinfunction "1_1") (pintype "passive"))
      (node (ref "C3") (pin "1") (pinfunction "1_1") (pintype "passive"))
      (node (ref "C4") (pin "1") (pinfunction "1_1") (pintype "passive"))
      (node (ref "C5") (pin "1") (pinfunction "1_1") (pintype "passive"))
      (node (ref "C6") (pin "1") (pinfunction "1_1") (pintype "passive"))
      (node (ref "C7") (pin "1") (pinfunction "1_1") (pintype "passive"))
      (node (ref "C8") (pin "1") (pinfunction "1_1") (pintype "passive"))
      (node (ref "C9") (pin "1") (pinfunction "1_1") (pintype "passive"))
      (node (ref "J1") (pin "1") (pinfunction "1_1") (pintype "passive"))
      (node (ref "J2") (pin "4") (pinfunction "ID_4") (pintype "passive"))
      (node (ref "J2") (pin "5") (pinfunction "GND_5") (pintype "passive"))
      (node (ref "J2") (pin "MOUNT") (pinfunction "MOUNT_MOUNT") (pintype "passive"))
      (node (ref "J3") (pin "3") (pinfunction "GND_3") (pintype "passive"))
      (node (ref "J3") (pin "5") (pinfunction "GND_5") (pintype "passive"))
      (node (ref "J3") (pin "9") (pinfunction "GND_DETECT_9") (pintype "passive"))
      (node (ref "J4") (pin "6") (pinfunction "VSS_6") (pintype "passive"))
      (node (ref "J4") (pin "CDA") (pinfunction "DETECT-GND_CDA") (pintype "passive"))
      (node (ref "J4") (pin "M") (pinfunction "MOUNT_M") (pintype "passive"))
      (node (ref "P16") (pin "1") (pinfunction "1_1") (pintype "passive"))
      (node (ref "P2") (pin "1") (pinfunction "1_1") (pintype "passive"))
      (node (ref "Q2") (pin "2") (pinfunction "S_2") (pintype "passive"))
      (node (ref "R1") (pin "2") (pinfunction "2_2") (pintype "passive"))
      (node (ref "R3") (pin "1") (pinfunction "1_1") (pintype "passive"))
      (node (ref "R9") (pin "1") (pinfunction "1_1") (pintype "passive"))
      (node (ref "RESET") (pin "1") (pinfunction "1_1") (pintype "passive"))
      (node (ref "RESET") (pin "S") (pinfunction "SHIELD_S") (pintype "passive"))
      (node (ref "U1") (pin "2") (pinfunction "VSS_2") (pintype "passive"))
      (node (ref "U2") (pin "2") (pinfunction "VSS_2") (pintype "passive"))
      (node (ref "U3") (pin "1") (pinfunction "GND_1") (pintype "passive"))
      (node (ref "U3") (pin "12") (pinfunction "GND_12") (pintype "passive"))
      (node (ref "U3") (pin "5") (pinfunction "GND_5") (pintype "passive"))
      (node (ref "U3") (pin "6") (pinfunction "GND_6") (pintype "passive"))
      (node (ref "U4") (pin "1") (pinfunction "GND_1") (pintype "passive"))
      (node (ref "U5") (pin "B1") (pinfunction "USB0_VSS_B1") (pintype "passive"))
      (node (ref "U5") (pin "B13") (pinfunction "VSS3_B13") (pintype "passive"))
      (node (ref "U5") (pin "B5") (pinfunction "VSS1_B5") (pintype "passive"))
      (node (ref "U5") (pin "B9") (pinfunction "VSS2_B9") (pintype "passive"))
      (node (ref "U5") (pin "H1") (pinfunction "VREFN_H1") (pintype "passive"))
      (node (ref "U5") (pin "H2") (pinfunction "VSSA_H2") (pintype "passive"))
      (node (ref "U5") (pin "M11") (pinfunction "VSS_PMU_M11") (pintype "passive"))
      (node (ref "U5") (pin "M12") (pinfunction "VSS_DCDC0_M12") (pintype "passive"))
      (node (ref "U5") (pin "N1") (pinfunction "VSS0_N1") (pintype "passive"))
      (node (ref "U5") (pin "N12") (pinfunction "VSS_DCDC1_N12") (pintype "passive"))
      (node (ref "U5") (pin "N5") (pinfunction "USB1_VSS_N5") (pintype "passive"))
      (node (ref "U6") (pin "2") (pinfunction "SELECT_2") (pintype "passive"))
      (node (ref "U6") (pin "3") (pinfunction "GND_3") (pintype "passive"))
      (node (ref "U8") (pin "5") (pinfunction "GND_5") (pintype "passive"))
    )
    (net (code "52") (name "Net-(D1-K)") (class "Default")
      (node (ref "C1") (pin "2") (pinfunction "1_2") (pintype "passive"))
      (node (ref "D1") (pin "2") (pinfunction "K_2") (pintype "passive"))
      (node (ref "D2") (pin "1") (pinfunction "A_1") (pintype "passive"))
      (node (ref "D3") (pin "2") (pinfunction "K_2") (pintype "passive"))
      (node (ref "Q1") (pin "1") (pinfunction "G_1") (pintype "passive"))
      (node (ref "R1") (pin "1") (pinfunction "1_1") (pintype "passive"))
      (node (ref "U1") (pin "4") (pinfunction "VDD_4") (pintype "passive"))
    )
    (net (code "53") (name "Net-(D2-K)") (class "Default")
      (node (ref "D2") (pin "2") (pinfunction "K_2") (pintype "passive"))
      (node (ref "Q1") (pin "2") (pinfunction "S_2") (pintype "passive"))
      (node (ref "SW1") (pin "1") (pinfunction "1_1") (pintype "passive"))
    )
    (net (code "54") (name "Net-(Q2-D)") (class "Default")
      (node (ref "Q2") (pin "3") (pinfunction "D_3") (pintype "passive"))
      (node (ref "R2") (pin "1") (pinfunction "1_1") (pintype "passive"))
    )
    (net (code "55") (name "Net-(U1-PROG)") (class "Default")
      (node (ref "R3") (pin "2") (pinfunction "2_2") (pintype "passive"))
      (node (ref "U1") (pin "5") (pinfunction "PROG_5") (pintype "passive"))
    )
    (net (code "56") (name "Net-(U3-LEDK)") (class "Default")
      (node (ref "R2") (pin "2") (pinfunction "2_2") (pintype "passive"))
      (node (ref "U3") (pin "2") (pinfunction "LEDK_2") (pintype "passive"))
    )
    (net (code "57") (name "Net-(U5-FB)") (class "Default")
      (node (ref "C10") (pin "2") (pinfunction "1_2") (pintype "passive"))
      (node (ref "C11") (pin "2") (pinfunction "1_2") (pintype "passive"))
      (node (ref "L1") (pin "1") (pinfunction "1_1") (pintype "passive"))
      (node (ref "U5") (pin "M9") (pinfunction "VDD_PMU_M9") (pintype "passive"))
      (node (ref "U5") (pin "N9") (pinfunction "FB_N9") (pintype "passive"))
    )
    (net (code "58") (name "Net-(U5-LX)") (class "Default")
      (node (ref "L1") (pin "2") (pinfunction "2_2") (pintype "passive"))
      (node (ref "U5") (pin "N11") (pinfunction "LX_N11") (pintype "passive"))
    )
    (net (code "59") (name "Net-(U5-USB1_VBUS)") (class "Default")
      (node (ref "R7") (pin "1") (pinfunction "1_1") (pintype "passive"))
      (node (ref "U5") (pin "N8") (pinfunction "USB1_VBUS_N8") (pintype "passive"))
    )
    (net (code "60") (name "Net-(U5-VDDA)") (class "Default")
      (node (ref "C12") (pin "1") (pinfunction "1_1") (pintype "passive"))
      (node (ref "C13") (pin "2") (pinfunction "1_2") (pintype "passive"))
      (node (ref "L2") (pin "2") (pinfunction "2_2") (pintype "passive"))
      (node (ref "U5") (pin "G1") (pinfunction "VREFP_G1") (pintype "passive"))
      (node (ref "U5") (pin "G2") (pinfunction "VDDA_G2") (pintype "passive"))
    )
    (net (code "61") (name "Net-(U5-XTAL32M_N)") (class "Default")
      (node (ref "C15") (pin "2") (pinfunction "1_2") (pintype "passive"))
      (node (ref "U5") (pin "M3") (pinfunction "XTAL32M_N_M3") (pintype "passive"))
      (node (ref "U7") (pin "1") (pinfunction "OSC1_1") (pintype "passive"))
    )
    (net (code "62") (name "Net-(U5-XTAL32M_P)") (class "Default")
      (node (ref "C14") (pin "2") (pinfunction "1_2") (pintype "passive"))
      (node (ref "U5") (pin "N3") (pinfunction "XTAL32M_P_N3") (pintype "passive"))
      (node (ref "U7") (pin "2") (pinfunction "OSC2_2") (pintype "passive"))
    )
    (net (code "63") (name "PWR_SWITCH") (class "Default")
      (node (ref "C3") (pin "2") (pinfunction "1_2") (pintype "passive"))
      (node (ref "P8") (pin "1") (pinfunction "1_1") (pintype "passive"))
      (node (ref "SW1") (pin "2") (pinfunction "2_2") (pintype "passive"))
      (node (ref "U2") (pin "1") (pinfunction "VIN_1") (pintype "passive"))
      (node (ref "U2") (pin "3") (pinfunction "~{SHDN}_3") (pintype "passive"))
    )
    (net (code "64") (name "unconnected-(J3-KEY-Pad7)") (class "Default")
      (node (ref "J3") (pin "7") (pinfunction "KEY_7") (pintype "passive+no_connect"))
    )
    (net (code "65") (name "unconnected-(J3-TDI-Pad8)") (class "Default")
      (node (ref "J3") (pin "8") (pinfunction "TDI_8") (pintype "passive+no_connect"))
    )
    (net (code "66") (name "unconnected-(U2-NC-Pad4)") (class "Default")
      (node (ref "U2") (pin "4") (pinfunction "NC_4") (pintype "passive+no_connect"))
    )
    (net (code "67") (name "unconnected-(U5-PIO0_1{slash}FC3_CTS_SDA_SSEL0{slash}CT_INP0{slash}SCT_GPI1{slash}SD1_CLK{slash}CMP0_OUT{slash}SECURE_GPIO0_1-PadF5)") (class "Default")
      (node (ref "U5") (pin "F5") (pinfunction "PIO0_1/FC3_CTS_SDA_SSEL0/CT_INP0/SCT_GPI1/SD1_CLK/CMP0_OUT/SECURE_GPIO0_1_F5") (pintype "passive+no_connect"))
    )
    (net (code "68") (name "unconnected-(U5-PIO0_4{slash}FC4_SCK{slash}CT_INP12{slash}SCT_GPI4{slash}FC3_CTS_SDA_SSEL0{slash}SECURE_GPIO0_4-PadE7)") (class "Default")
      (node (ref "U5") (pin "E7") (pinfunction "PIO0_4/FC4_SCK/CT_INP12/SCT_GPI4/FC3_CTS_SDA_SSEL0/SECURE_GPIO0_4_E7") (pintype "passive+no_connect"))
    )
    (net (code "69") (name "unconnected-(U5-PIO0_7{slash}FC3_RTS_SCL_SSEL1{slash}SD0_CLK{slash}FC5_SCK{slash}FC1_SCK{slash}SECURE_GPIO0_7-PadG5)") (class "Default")
      (node (ref "U5") (pin "G5") (pinfunction "PIO0_7/FC3_RTS_SCL_SSEL1/SD0_CLK/FC5_SCK/FC1_SCK/SECURE_GPIO0_7_G5") (pintype "passive+no_connect"))
    )
    (net (code "70") (name "unconnected-(U5-PIO0_8{slash}FC3_SSEL3{slash}SD0_CMD{slash}FC5_RXD_SDA_MOSI_DATA{slash}SWO{slash}SECURE_GPIO0_8-PadM2)") (class "Default")
      (node (ref "U5") (pin "M2") (pinfunction "PIO0_8/FC3_SSEL3/SD0_CMD/FC5_RXD_SDA_MOSI_DATA/SWO/SECURE_GPIO0_8_M2") (pintype "passive+no_connect"))
    )
    (net (code "71") (name "unconnected-(U5-PIO0_17{slash}FC4_SSEL2{slash}SD0_CARD_DET_N{slash}SCT_GPI7{slash}SCT0_OUT0{slash}SD0_CARD_INT_N{slash}PLU_IN2{slash}SECURE_GPIO0_17-PadG3)") (class "Default")
      (node (ref "U5") (pin "G3") (pinfunction "PIO0_17/FC4_SSEL2/SD0_CARD_DET_N/SCT_GPI7/SCT0_OUT0/SD0_CARD_INT_N/PLU_IN2/SECURE_GPIO0_17_G3") (pintype "passive+no_connect"))
    )
    (net (code "72") (name "unconnected-(U5-PIO0_18{slash}FC4_CTS_SDA_SSEL0{slash}SD0_WR_PRT{slash}CTIMER1_MAT0{slash}SCT0_OUT1{slash}PLU_IN3{slash}SECURE_GPIO0_18{slash}ACMP0_C-PadH9)") (class "Default")
      (node (ref "U5") (pin "H9") (pinfunction "PIO0_18/FC4_CTS_SDA_SSEL0/SD0_WR_PRT/CTIMER1_MAT0/SCT0_OUT1/PLU_IN3/SECURE_GPIO0_18/ACMP0_C_H9") (pintype "passive+no_connect"))
    )
    (net (code "73") (name "unconnected-(U5-PIO0_19{slash}FC4_RTS_SCL_SSEL1{slash}UTICK_CAP0{slash}CTIMER0_MAT2{slash}SCT0_OUT2{slash}FC7_TXD_SCL_MISO_WS{slash}PLU_IN4{slash}SECURE_GPIO0_19-PadE6)") (class "Default")
      (node (ref "U5") (pin "E6") (pinfunction "PIO0_19/FC4_RTS_SCL_SSEL1/UTICK_CAP0/CTIMER0_MAT2/SCT0_OUT2/FC7_TXD_SCL_MISO_WS/PLU_IN4/SECURE_GPIO0_19_E6") (pintype "passive+no_connect"))
    )
    (net (code "74") (name "unconnected-(U5-PIO0_20{slash}FC3_CTS_SDA_SSEL0{slash}CTIMER1_MAT1{slash}CT_INP15{slash}SCT_GPI2{slash}FC7_RXD_SDA_MOSI_DATA{slash}HS_SPI_SSEL0{slash}PLU_IN5{slash}SECURE_GPIO0_20{slash}FC4_TXD_SCL_MISO_WS-PadB12)") (class "Default")
      (node (ref "U5") (pin "B12") (pinfunction "PIO0_20/FC3_CTS_SDA_SSEL0/CTIMER1_MAT1/CT_INP15/SCT_GPI2/FC7_RXD_SDA_MOSI_DATA/HS_SPI_SSEL0/PLU_IN5/SECURE_GPIO0_20/FC4_TXD_SCL_MISO_WS_B12") (pintype "passive"))
    )
    (net (code "75") (name "unconnected-(U5-PIO0_22{slash}FC6_TXD_SCL_MISO_WS{slash}UTICK_CAP1{slash}CT_INP15{slash}SCT0_OUT3{slash}USB0_VBUS{slash}SD1_D0{slash}PLU_OUT7{slash}SECURE_GPIO0_22-PadE9)") (class "Default")
      (node (ref "U5") (pin "E9") (pinfunction "PIO0_22/FC6_TXD_SCL_MISO_WS/UTICK_CAP1/CT_INP15/SCT0_OUT3/USB0_VBUS/SD1_D0/PLU_OUT7/SECURE_GPIO0_22_E9") (pintype "passive+no_connect"))
    )
    (net (code "76") (name "unconnected-(U5-PIO1_0{slash}FC0_RTS_SCL_SSEL1{slash}SD0_D3{slash}CT_INP2{slash}SCT_GPI4{slash}PLU_OUT3{slash}ADC0_11-PadE1)") (class "Default")
      (node (ref "U5") (pin "E1") (pinfunction "PIO1_0/FC0_RTS_SCL_SSEL1/SD0_D3/CT_INP2/SCT_GPI4/PLU_OUT3/ADC0_11_E1") (pintype "passive+no_connect"))
    )
    (net (code "77") (name "unconnected-(U5-PIO1_7{slash}FC0_RTS_SCL_SSEL1{slash}SD0_D1{slash}CTIMER2_MAT2{slash}SCT_GPI4-PadJ5)") (class "Default")
      (node (ref "U5") (pin "J5") (pinfunction "PIO1_7/FC0_RTS_SCL_SSEL1/SD0_D1/CTIMER2_MAT2/SCT_GPI4_J5") (pintype "passive+no_connect"))
    )
    (net (code "78") (name "unconnected-(U5-PIO1_9{slash}FC1_SCK{slash}CT_INP4{slash}SCT0_OUT2{slash}FC4_CTS_SDA_SSEL0{slash}ADC0_12-PadC1)") (class "Default")
      (node (ref "U5") (pin "C1") (pinfunction "PIO1_9/FC1_SCK/CT_INP4/SCT0_OUT2/FC4_CTS_SDA_SSEL0/ADC0_12_C1") (pintype "passive+no_connect"))
    )
    (net (code "79") (name "unconnected-(U5-PIO1_10{slash}FC1_RXD_SDA_MOSI_DATA{slash}CTIMER1_MAT0{slash}SCT0_OUT3-PadJ7)") (class "Default")
      (node (ref "U5") (pin "J7") (pinfunction "PIO1_10/FC1_RXD_SDA_MOSI_DATA/CTIMER1_MAT0/SCT0_OUT3_J7") (pintype "passive+no_connect"))
    )
    (net (code "80") (name "unconnected-(U5-PIO1_11{slash}FC1_TXD_SCL_MISO_WS{slash}CT_INP5{slash}USB0_VBUS-PadG6)") (class "Default")
      (node (ref "U5") (pin "G6") (pinfunction "PIO1_11/FC1_TXD_SCL_MISO_WS/CT_INP5/USB0_VBUS_G6") (pintype "passive+no_connect"))
    )
    (net (code "81") (name "unconnected-(U5-PIO1_12{slash}FC6_SCK{slash}CTIMER1_MAT1{slash}USB0_PORTPWRN{slash}HS_SPI_SSEL2-PadF12)") (class "Default")
      (node (ref "U5") (pin "F12") (pinfunction "PIO1_12/FC6_SCK/CTIMER1_MAT1/USB0_PORTPWRN/HS_SPI_SSEL2_F12") (pintype "passive+no_connect"))
    )
    (net (code "82") (name "unconnected-(U5-PIO1_14{slash}UTICK_CAP2{slash}CTIMER1_MAT2{slash}FC5_CTS_SDA_SSEL0{slash}USB0_LEDN{slash}SD1_CMD{slash}ACMP0_D-PadL7)") (class "Default")
      (node (ref "U5") (pin "L7") (pinfunction "PIO1_14/UTICK_CAP2/CTIMER1_MAT2/FC5_CTS_SDA_SSEL0/USB0_LEDN/SD1_CMD/ACMP0_D_L7") (pintype "passive+no_connect"))
    )
    (net (code "83") (name "unconnected-(U5-PIO1_15{slash}UTICK_CAP3{slash}CT_INP7{slash}FC5_RTS_SCL_SSEL1{slash}FC4_RTS_SCL_SSEL1{slash}SD1_D2-PadB6)") (class "Default")
      (node (ref "U5") (pin "B6") (pinfunction "PIO1_15/UTICK_CAP3/CT_INP7/FC5_RTS_SCL_SSEL1/FC4_RTS_SCL_SSEL1/SD1_D2_B6") (pintype "passive+no_connect"))
    )
    (net (code "84") (name "unconnected-(U5-PIO1_18{slash}SD1_POW_EN{slash}SCT0_OUT5{slash}PLU_OUT0-PadG9)") (class "Default")
      (node (ref "U5") (pin "G9") (pinfunction "PIO1_18/SD1_POW_EN/SCT0_OUT5/PLU_OUT0_G9") (pintype "passive+no_connect"))
    )
    (net (code "85") (name "unconnected-(U5-PIO1_20{slash}FC7_RTS_SCL_SSEL1{slash}CT_INP14{slash}FC4_TXD_SCL_MISO_WS{slash}PLU_OUT2-PadC2)") (class "Default")
      (node (ref "U5") (pin "C2") (pinfunction "PIO1_20/FC7_RTS_SCL_SSEL1/CT_INP14/FC4_TXD_SCL_MISO_WS/PLU_OUT2_C2") (pintype "passive+no_connect"))
    )
    (net (code "86") (name "unconnected-(U5-PIO1_21{slash}FC7_CTS_SDA_SSEL0{slash}CTIMER3_MAT2{slash}FC4_RXD_SDA_MOSI_DATA{slash}PLU_OUT3-PadM7)") (class "Default")
      (node (ref "U5") (pin "M7") (pinfunction "PIO1_21/FC7_CTS_SDA_SSEL0/CTIMER3_MAT2/FC4_RXD_SDA_MOSI_DATA/PLU_OUT3_M7") (pintype "passive+no_connect"))
    )
    (net (code "87") (name "unconnected-(U5-PIO1_23{slash}FC2_SCK{slash}SCT0_OUT0{slash}SD1_D3{slash}FC3_SSEL2{slash}PLU_OUT5-PadJ8)") (class "Default")
      (node (ref "U5") (pin "J8") (pinfunction "PIO1_23/FC2_SCK/SCT0_OUT0/SD1_D3/FC3_SSEL2/PLU_OUT5_J8") (pintype "passive+no_connect"))
    )
    (net (code "88") (name "unconnected-(U5-PIO1_24{slash}FC2_RXD_SDA_MOSI_DATA{slash}SCT0_OUT1{slash}SD1_D1{slash}FC3_SSEL3{slash}PLU_OUT6-PadF6)") (class "Default")
      (node (ref "U5") (pin "F6") (pinfunction "PIO1_24/FC2_RXD_SDA_MOSI_DATA/SCT0_OUT1/SD1_D1/FC3_SSEL3/PLU_OUT6_F6") (pintype "passive+no_connect"))
    )
    (net (code "89") (name "unconnected-(U5-PIO1_25{slash}FC2_TXD_SCL_MISO_WS{slash}SCT0_OUT2{slash}SD1_D0{slash}UTICK_CAP0{slash}PLU_CLKIN-PadB8)") (class "Default")
      (node (ref "U5") (pin "B8") (pinfunction "PIO1_25/FC2_TXD_SCL_MISO_WS/SCT0_OUT2/SD1_D0/UTICK_CAP0/PLU_CLKIN_B8") (pintype "passive+no_connect"))
    )
    (net (code "90") (name "unconnected-(U5-PIO1_29{slash}FC7_RXD_SDA_MOSI_DATA{slash}SD0_D6{slash}SCT_GPI6{slash}USB1_PORTPWRN{slash}USB1_FRAME{slash}PLU_IN2-PadG8)") (class "Default")
      (node (ref "U5") (pin "G8") (pinfunction "PIO1_29/FC7_RXD_SDA_MOSI_DATA/SD0_D6/SCT_GPI6/USB1_PORTPWRN/USB1_FRAME/PLU_IN2_G8") (pintype "passive+no_connect"))
    )
    (net (code "91") (name "unconnected-(U5-PIO1_30{slash}FC7_TXD_SCL_MISO_WS{slash}SD0_D7{slash}SCT_GPI7{slash}USB1_OVERCURRENTN{slash}USB1_LEDN{slash}PLU_IN1-PadF9)") (class "Default")
      (node (ref "U5") (pin "F9") (pinfunction "PIO1_30/FC7_TXD_SCL_MISO_WS/SD0_D7/SCT_GPI7/USB1_OVERCURRENTN/USB1_LEDN/PLU_IN1_F9") (pintype "passive+no_connect"))
    )
    (net (code "92") (name "unconnected-(U5-PIO1_31{slash}MCLK{slash}SD1_CLK{slash}CTIMER0_MAT2{slash}SCT0_OUT6{slash}PLU_IN0-PadH6)") (class "Default")
      (node (ref "U5") (pin "H6") (pinfunction "PIO1_31/MCLK/SD1_CLK/CTIMER0_MAT2/SCT0_OUT6/PLU_IN0_H6") (pintype "passive+no_connect"))
    )
    (net (code "93") (name "unconnected-(U5-USB0_DM-PadA1)") (class "Default")
      (node (ref "U5") (pin "A1") (pinfunction "USB0_DM_A1") (pintype "passive+no_connect"))
    )
    (net (code "94") (name "unconnected-(U5-USB0_DP-PadA2)") (class "Default")
      (node (ref "U5") (pin "A2") (pinfunction "USB0_DP_A2") (pintype "passive+no_connect"))
    )
    (net (code "95") (name "unconnected-(U5-XTAL32K_N-PadJ12)") (class "Default")
      (node (ref "U5") (pin "J12") (pinfunction "XTAL32K_N_J12") (pintype "passive+no_connect"))
    )
    (net (code "96") (name "unconnected-(U5-XTAL32K_P-PadJ13)") (class "Default")
      (node (ref "U5") (pin "J13") (pinfunction "XTAL32K_P_J13") (pintype "passive+no_connect"))
    )
  )
)
